# untitled.net
KiCad netlist of a schematic drawn in EAGLE
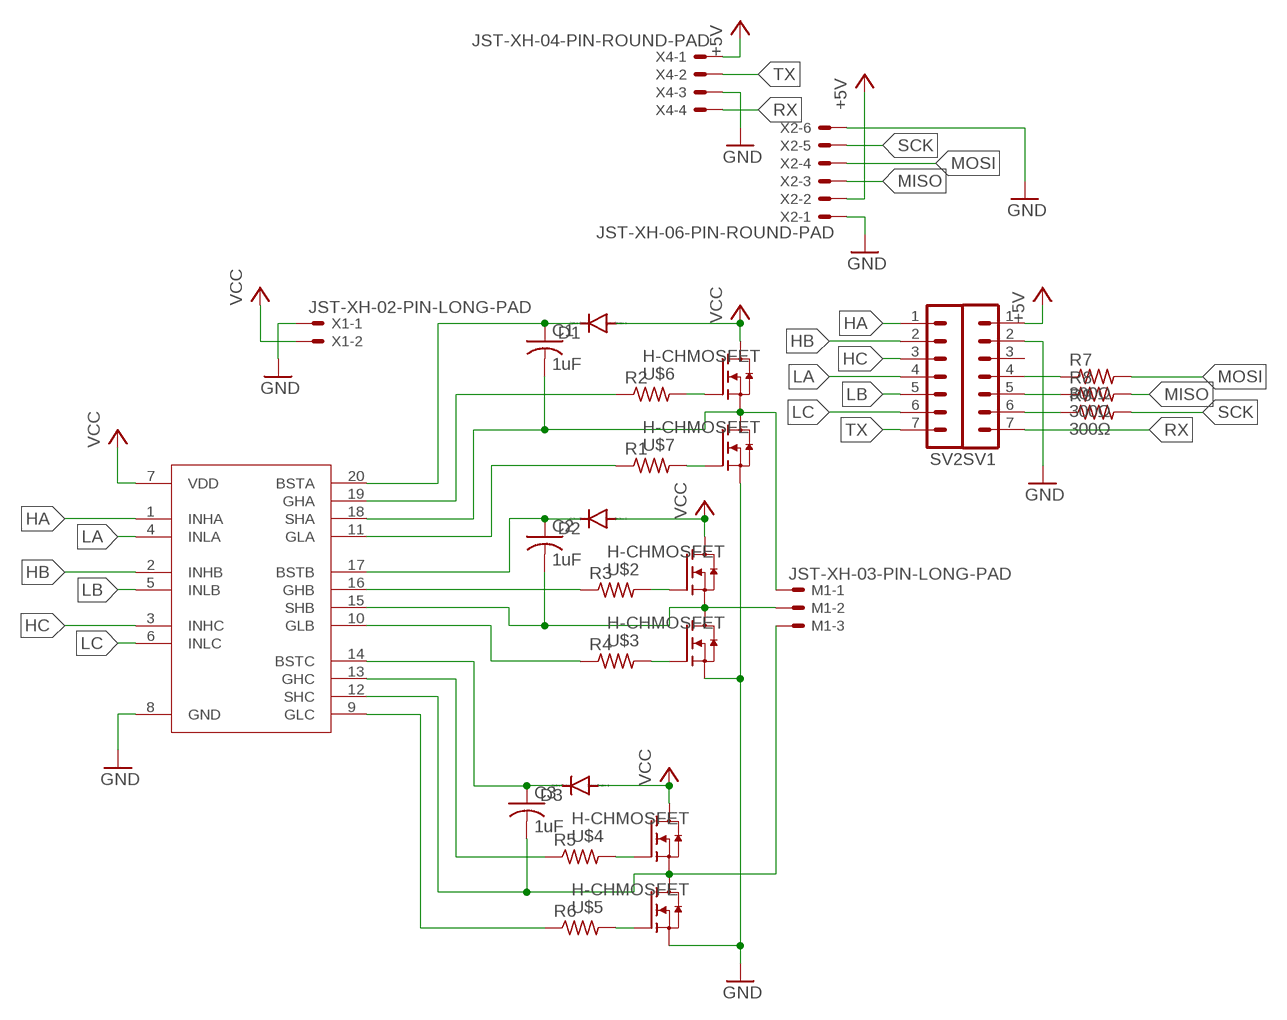
[diagram p0: schematic, sheet 1]

(export (version "E")
  (design (tool "Eeschema 10.0.6"))
  (components
    (comp (ref "C1")
      (value "1uF")
      (footprint "eagle-import:C2012")
      (libsource (lib "eagle-import") (part "C-USC2012"))
    )
    (comp (ref "C2")
      (value "1uF")
      (footprint "eagle-import:C2012")
      (libsource (lib "eagle-import") (part "C-USC2012"))
    )
    (comp (ref "C3")
      (value "1uF")
      (footprint "eagle-import:C2012")
      (libsource (lib "eagle-import") (part "C-USC2012"))
    )
    (comp (ref "D1")
      (value "DIODE-DO-214AC")
      (footprint "eagle-import:DO-214AC")
      (libsource (lib "eagle-import") (part "DIODE-DO-214AC"))
    )
    (comp (ref "D2")
      (value "DIODE-DO-214AC")
      (footprint "eagle-import:DO-214AC")
      (libsource (lib "eagle-import") (part "DIODE-DO-214AC"))
    )
    (comp (ref "D3")
      (value "DIODE-DO-214AC")
      (footprint "eagle-import:DO-214AC")
      (libsource (lib "eagle-import") (part "DIODE-DO-214AC"))
    )
    (comp (ref "M1")
      (value "JST-XH-03-PIN-LONG-PAD")
      (footprint "eagle-import:JST-XH-03-PACKAGE-LONG-PAD")
      (libsource (lib "eagle-import") (part "JST-XH-03-PIN-LONG-PAD"))
    )
    (comp (ref "R1")
      (value "R-US_M2012")
      (footprint "eagle-import:M2012")
      (libsource (lib "eagle-import") (part "R-US_M2012"))
    )
    (comp (ref "R2")
      (value "R-US_M2012")
      (footprint "eagle-import:M2012")
      (libsource (lib "eagle-import") (part "R-US_M2012"))
    )
    (comp (ref "R3")
      (value "R-US_M2012")
      (footprint "eagle-import:M2012")
      (libsource (lib "eagle-import") (part "R-US_M2012"))
    )
    (comp (ref "R4")
      (value "R-US_M2012")
      (footprint "eagle-import:M2012")
      (libsource (lib "eagle-import") (part "R-US_M2012"))
    )
    (comp (ref "R5")
      (value "R-US_M2012")
      (footprint "eagle-import:M2012")
      (libsource (lib "eagle-import") (part "R-US_M2012"))
    )
    (comp (ref "R6")
      (value "R-US_M2012")
      (footprint "eagle-import:M2012")
      (libsource (lib "eagle-import") (part "R-US_M2012"))
    )
    (comp (ref "R7")
      (value "300Ω")
      (footprint "eagle-import:M2012")
      (libsource (lib "eagle-import") (part "R-US_M2012"))
    )
    (comp (ref "R8")
      (value "300Ω")
      (footprint "eagle-import:M2012")
      (libsource (lib "eagle-import") (part "R-US_M2012"))
    )
    (comp (ref "R9")
      (value "300Ω")
      (footprint "eagle-import:M2012")
      (libsource (lib "eagle-import") (part "R-US_M2012"))
    )
    (comp (ref "SV1")
      (value "MA07-1")
      (footprint "eagle-import:MA07-1")
      (libsource (lib "eagle-import") (part "MA07-1"))
    )
    (comp (ref "SV2")
      (value "MA07-1")
      (footprint "eagle-import:MA07-1")
      (libsource (lib "eagle-import") (part "MA07-1"))
    )
    (comp (ref "U$1")
      (value "DRV8300NIPWR")
      (footprint "eagle-import:SOIC65P640X120-20N")
      (libsource (lib "eagle-import") (part "DRV8300NIPWR"))
    )
    (comp (ref "U$2")
      (value "H-CHMOSFET")
      (footprint "eagle-import:DPAK228P990X238-4N")
      (libsource (lib "eagle-import") (part "H-CHMOSFET"))
    )
    (comp (ref "U$3")
      (value "H-CHMOSFET")
      (footprint "eagle-import:DPAK228P990X238-4N")
      (libsource (lib "eagle-import") (part "H-CHMOSFET"))
    )
    (comp (ref "U$4")
      (value "H-CHMOSFET")
      (footprint "eagle-import:DPAK228P990X238-4N")
      (libsource (lib "eagle-import") (part "H-CHMOSFET"))
    )
    (comp (ref "U$5")
      (value "H-CHMOSFET")
      (footprint "eagle-import:DPAK228P990X238-4N")
      (libsource (lib "eagle-import") (part "H-CHMOSFET"))
    )
    (comp (ref "U$6")
      (value "H-CHMOSFET")
      (footprint "eagle-import:DPAK228P990X238-4N")
      (libsource (lib "eagle-import") (part "H-CHMOSFET"))
    )
    (comp (ref "U$7")
      (value "H-CHMOSFET")
      (footprint "eagle-import:DPAK228P990X238-4N")
      (libsource (lib "eagle-import") (part "H-CHMOSFET"))
    )
    (comp (ref "X1")
      (value "JST-XH-02-PIN-LONG-PAD")
      (footprint "eagle-import:JST-XH-02-PACKAGE-LONG-PAD")
      (libsource (lib "eagle-import") (part "JST-XH-02-PIN-LONG-PAD"))
    )
    (comp (ref "X2")
      (value "JST-XH-06-PIN-ROUND-PAD")
      (footprint "eagle-import:JST-XH-06-PACKAGE-ROUND-PAD")
      (libsource (lib "eagle-import") (part "JST-XH-06-PIN-ROUND-PAD"))
    )
    (comp (ref "X4")
      (value "JST-XH-04-PIN-ROUND-PAD")
      (footprint "eagle-import:JST-XH-04-PACKAGE-ROUND-PAD")
      (libsource (lib "eagle-import") (part "JST-XH-04-PIN-ROUND-PAD"))
    )
  )
  (nets
    (net (code "1") (name "+5V") (class "Default")
      (node (ref "SV1") (pin "1") (pinfunction "1_1") (pintype "passive"))
      (node (ref "X2") (pin "2") (pinfunction "S_2") (pintype "passive"))
      (node (ref "X4") (pin "1") (pinfunction "S_1") (pintype "passive"))
    )
    (net (code "2") (name "GND") (class "Default")
      (node (ref "SV1") (pin "2") (pinfunction "2_2") (pintype "passive"))
      (node (ref "U$1") (pin "8") (pinfunction "GND_8") (pintype "bidirectional"))
      (node (ref "U$3") (pin "3") (pinfunction "S_3") (pintype "passive"))
      (node (ref "U$5") (pin "3") (pinfunction "S_3") (pintype "passive"))
      (node (ref "U$7") (pin "3") (pinfunction "S_3") (pintype "passive"))
      (node (ref "X1") (pin "1") (pinfunction "S_1") (pintype "passive"))
      (node (ref "X2") (pin "1") (pinfunction "S_1") (pintype "passive"))
      (node (ref "X2") (pin "6") (pinfunction "S_6") (pintype "passive"))
      (node (ref "X4") (pin "3") (pinfunction "S_3") (pintype "passive"))
    )
    (net (code "3") (name "HA") (class "Default")
      (node (ref "SV2") (pin "1") (pinfunction "1_1") (pintype "passive"))
      (node (ref "U$1") (pin "1") (pinfunction "INHA_1") (pintype "bidirectional"))
    )
    (net (code "4") (name "HB") (class "Default")
      (node (ref "SV2") (pin "2") (pinfunction "2_2") (pintype "passive"))
      (node (ref "U$1") (pin "2") (pinfunction "INHB_2") (pintype "bidirectional"))
    )
    (net (code "5") (name "HC") (class "Default")
      (node (ref "SV2") (pin "3") (pinfunction "3_3") (pintype "passive"))
      (node (ref "U$1") (pin "3") (pinfunction "INHC_3") (pintype "bidirectional"))
    )
    (net (code "6") (name "LA") (class "Default")
      (node (ref "SV2") (pin "4") (pinfunction "4_4") (pintype "passive"))
      (node (ref "U$1") (pin "4") (pinfunction "INLA_4") (pintype "bidirectional"))
    )
    (net (code "7") (name "LB") (class "Default")
      (node (ref "SV2") (pin "5") (pinfunction "5_5") (pintype "passive"))
      (node (ref "U$1") (pin "5") (pinfunction "INLB_5") (pintype "bidirectional"))
    )
    (net (code "8") (name "LC") (class "Default")
      (node (ref "SV2") (pin "6") (pinfunction "6_6") (pintype "passive"))
      (node (ref "U$1") (pin "6") (pinfunction "INLC_6") (pintype "bidirectional"))
    )
    (net (code "9") (name "MISO") (class "Default")
      (node (ref "R8") (pin "2") (pinfunction "2_2") (pintype "passive"))
      (node (ref "X2") (pin "3") (pinfunction "S_3") (pintype "passive"))
    )
    (net (code "10") (name "MOSI") (class "Default")
      (node (ref "R7") (pin "2") (pinfunction "2_2") (pintype "passive"))
      (node (ref "X2") (pin "4") (pinfunction "S_4") (pintype "passive"))
    )
    (net (code "11") (name "Net-(M1A-S)") (class "Default")
      (node (ref "C1") (pin "2") (pinfunction "2_2") (pintype "passive"))
      (node (ref "M1") (pin "1") (pinfunction "S_1") (pintype "passive"))
      (node (ref "U$1") (pin "18") (pinfunction "SHA_18") (pintype "bidirectional"))
      (node (ref "U$6") (pin "3") (pinfunction "S_3") (pintype "passive"))
      (node (ref "U$7") (pin "4") (pinfunction "D_4") (pintype "passive"))
    )
    (net (code "12") (name "Net-(M1B-S)") (class "Default")
      (node (ref "C2") (pin "2") (pinfunction "2_2") (pintype "passive"))
      (node (ref "M1") (pin "2") (pinfunction "S_2") (pintype "passive"))
      (node (ref "U$1") (pin "15") (pinfunction "SHB_15") (pintype "bidirectional"))
      (node (ref "U$2") (pin "3") (pinfunction "S_3") (pintype "passive"))
      (node (ref "U$3") (pin "4") (pinfunction "D_4") (pintype "passive"))
    )
    (net (code "13") (name "Net-(M1C-S)") (class "Default")
      (node (ref "C3") (pin "2") (pinfunction "2_2") (pintype "passive"))
      (node (ref "M1") (pin "3") (pinfunction "S_3") (pintype "passive"))
      (node (ref "U$1") (pin "12") (pinfunction "SHC_12") (pintype "bidirectional"))
      (node (ref "U$4") (pin "3") (pinfunction "S_3") (pintype "passive"))
      (node (ref "U$5") (pin "4") (pinfunction "D_4") (pintype "passive"))
    )
    (net (code "14") (name "Net-(R7-Pad1)") (class "Default")
      (node (ref "R7") (pin "1") (pinfunction "1_1") (pintype "passive"))
      (node (ref "SV1") (pin "4") (pinfunction "4_4") (pintype "passive"))
    )
    (net (code "15") (name "Net-(R8-Pad1)") (class "Default")
      (node (ref "R8") (pin "1") (pinfunction "1_1") (pintype "passive"))
      (node (ref "SV1") (pin "5") (pinfunction "5_5") (pintype "passive"))
    )
    (net (code "16") (name "Net-(R9-Pad1)") (class "Default")
      (node (ref "R9") (pin "1") (pinfunction "1_1") (pintype "passive"))
      (node (ref "SV1") (pin "6") (pinfunction "6_6") (pintype "passive"))
    )
    (net (code "17") (name "Net-(U$1-BSTA)") (class "Default")
      (node (ref "C1") (pin "1") (pinfunction "1_1") (pintype "passive"))
      (node (ref "D1") (pin "C") (pinfunction "C_C") (pintype "passive"))
      (node (ref "U$1") (pin "20") (pinfunction "BSTA_20") (pintype "bidirectional"))
    )
    (net (code "18") (name "Net-(U$1-BSTB)") (class "Default")
      (node (ref "C2") (pin "1") (pinfunction "1_1") (pintype "passive"))
      (node (ref "D2") (pin "C") (pinfunction "C_C") (pintype "passive"))
      (node (ref "U$1") (pin "17") (pinfunction "BSTB_17") (pintype "bidirectional"))
    )
    (net (code "19") (name "Net-(U$1-BSTC)") (class "Default")
      (node (ref "C3") (pin "1") (pinfunction "1_1") (pintype "passive"))
      (node (ref "D3") (pin "C") (pinfunction "C_C") (pintype "passive"))
      (node (ref "U$1") (pin "14") (pinfunction "BSTC_14") (pintype "bidirectional"))
    )
    (net (code "20") (name "Net-(U$1-GHA)") (class "Default")
      (node (ref "R2") (pin "1") (pinfunction "1_1") (pintype "passive"))
      (node (ref "U$1") (pin "19") (pinfunction "GHA_19") (pintype "bidirectional"))
    )
    (net (code "21") (name "Net-(U$1-GHB)") (class "Default")
      (node (ref "R3") (pin "1") (pinfunction "1_1") (pintype "passive"))
      (node (ref "U$1") (pin "16") (pinfunction "GHB_16") (pintype "bidirectional"))
    )
    (net (code "22") (name "Net-(U$1-GHC)") (class "Default")
      (node (ref "R5") (pin "1") (pinfunction "1_1") (pintype "passive"))
      (node (ref "U$1") (pin "13") (pinfunction "GHC_13") (pintype "bidirectional"))
    )
    (net (code "23") (name "Net-(U$1-GLA)") (class "Default")
      (node (ref "R1") (pin "1") (pinfunction "1_1") (pintype "passive"))
      (node (ref "U$1") (pin "11") (pinfunction "GLA_11") (pintype "bidirectional"))
    )
    (net (code "24") (name "Net-(U$1-GLB)") (class "Default")
      (node (ref "R4") (pin "1") (pinfunction "1_1") (pintype "passive"))
      (node (ref "U$1") (pin "10") (pinfunction "GLB_10") (pintype "bidirectional"))
    )
    (net (code "25") (name "Net-(U$1-GLC)") (class "Default")
      (node (ref "R6") (pin "1") (pinfunction "1_1") (pintype "passive"))
      (node (ref "U$1") (pin "9") (pinfunction "GLC_9") (pintype "bidirectional"))
    )
    (net (code "26") (name "Net-(U$2-G)") (class "Default")
      (node (ref "R3") (pin "2") (pinfunction "2_2") (pintype "passive"))
      (node (ref "U$2") (pin "1") (pinfunction "G_1") (pintype "passive"))
    )
    (net (code "27") (name "Net-(U$3-G)") (class "Default")
      (node (ref "R4") (pin "2") (pinfunction "2_2") (pintype "passive"))
      (node (ref "U$3") (pin "1") (pinfunction "G_1") (pintype "passive"))
    )
    (net (code "28") (name "Net-(U$4-G)") (class "Default")
      (node (ref "R5") (pin "2") (pinfunction "2_2") (pintype "passive"))
      (node (ref "U$4") (pin "1") (pinfunction "G_1") (pintype "passive"))
    )
    (net (code "29") (name "Net-(U$5-G)") (class "Default")
      (node (ref "R6") (pin "2") (pinfunction "2_2") (pintype "passive"))
      (node (ref "U$5") (pin "1") (pinfunction "G_1") (pintype "passive"))
    )
    (net (code "30") (name "Net-(U$6-G)") (class "Default")
      (node (ref "R2") (pin "2") (pinfunction "2_2") (pintype "passive"))
      (node (ref "U$6") (pin "1") (pinfunction "G_1") (pintype "passive"))
    )
    (net (code "31") (name "Net-(U$7-G)") (class "Default")
      (node (ref "R1") (pin "2") (pinfunction "2_2") (pintype "passive"))
      (node (ref "U$7") (pin "1") (pinfunction "G_1") (pintype "passive"))
    )
    (net (code "32") (name "RX") (class "Default")
      (node (ref "SV1") (pin "7") (pinfunction "7_7") (pintype "passive"))
      (node (ref "X4") (pin "4") (pinfunction "S_4") (pintype "passive"))
    )
    (net (code "33") (name "SCK") (class "Default")
      (node (ref "R9") (pin "2") (pinfunction "2_2") (pintype "passive"))
      (node (ref "X2") (pin "5") (pinfunction "S_5") (pintype "passive"))
    )
    (net (code "34") (name "TX") (class "Default")
      (node (ref "SV2") (pin "7") (pinfunction "7_7") (pintype "passive"))
      (node (ref "X4") (pin "2") (pinfunction "S_2") (pintype "passive"))
    )
    (net (code "35") (name "VCC") (class "Default")
      (node (ref "D1") (pin "A") (pinfunction "A_A") (pintype "passive"))
      (node (ref "D2") (pin "A") (pinfunction "A_A") (pintype "passive"))
      (node (ref "D3") (pin "A") (pinfunction "A_A") (pintype "passive"))
      (node (ref "U$1") (pin "7") (pinfunction "VDD_7") (pintype "bidirectional"))
      (node (ref "U$2") (pin "4") (pinfunction "D_4") (pintype "passive"))
      (node (ref "U$4") (pin "4") (pinfunction "D_4") (pintype "passive"))
      (node (ref "U$6") (pin "4") (pinfunction "D_4") (pintype "passive"))
      (node (ref "X1") (pin "2") (pinfunction "S_2") (pintype "passive"))
    )
    (net (code "36") (name "unconnected-(SV1-Pad3)") (class "Default")
      (node (ref "SV1") (pin "3") (pinfunction "3_3") (pintype "passive"))
    )
  )
)
